# TubeBoard-Holder.net
KiCad netlist of a schematic drawn in EAGLE
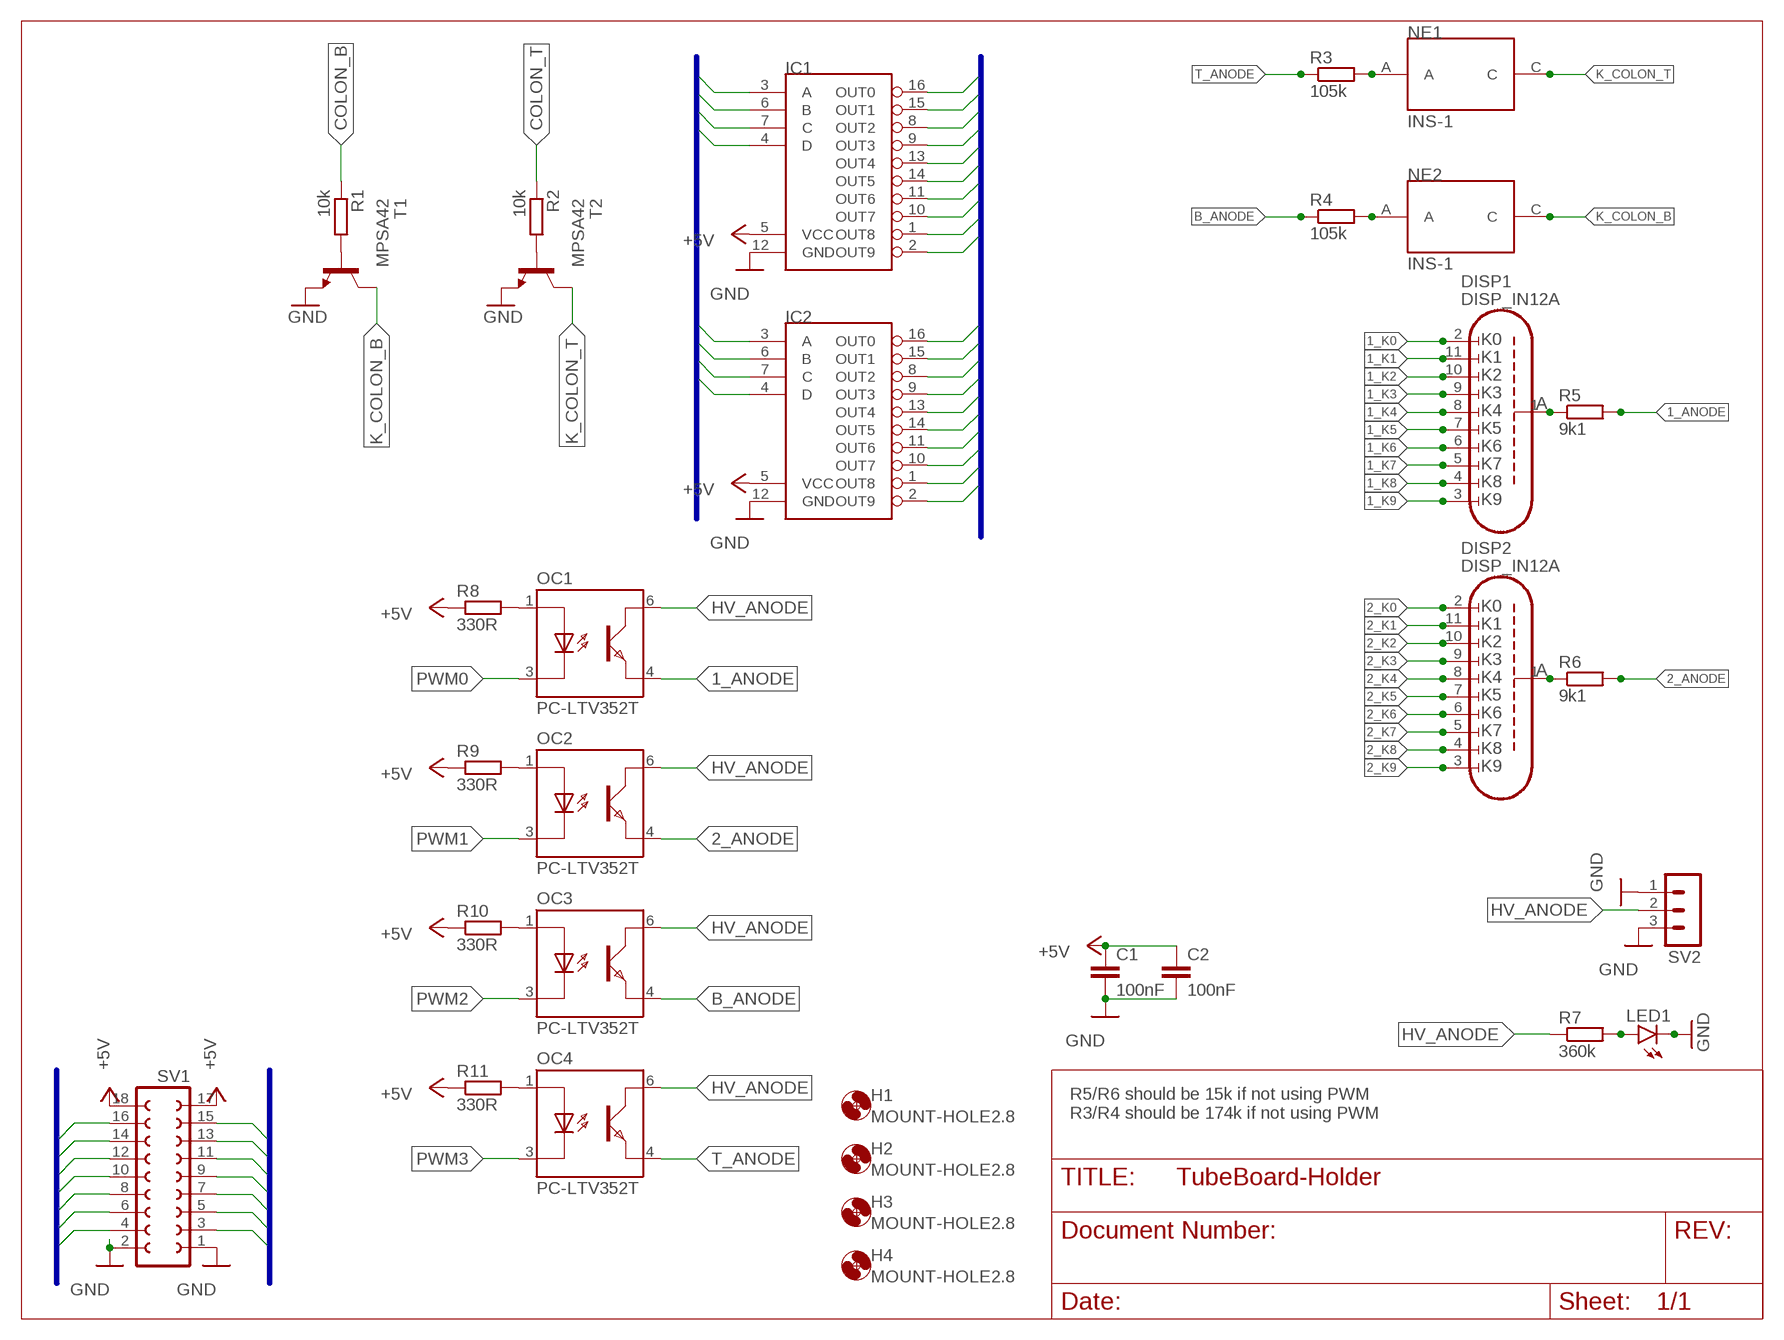
[diagram p0: schematic, sheet 1]

(export (version "E")
  (design (tool "Eeschema 10.0.6"))
  (components
    (comp (ref "C1")
      (value "100nF")
      (footprint "eagle-import:C1206")
      (libsource (lib "eagle-import") (part "C-EUC1206"))
    )
    (comp (ref "C2")
      (value "100nF")
      (footprint "eagle-import:C1206")
      (libsource (lib "eagle-import") (part "C-EUC1206"))
    )
    (comp (ref "DISP1")
      (value "DISP_IN12A")
      (footprint "eagle-import:DISP_IN-12_SOCKET")
      (libsource (lib "eagle-import") (part "DISP_IN12A"))
    )
    (comp (ref "DISP2")
      (value "DISP_IN12A")
      (footprint "eagle-import:DISP_IN-12_SOCKET")
      (libsource (lib "eagle-import") (part "DISP_IN12A"))
    )
    (comp (ref "H1")
      (value "MOUNT-HOLE2.8")
      (footprint "eagle-import:2,8")
      (libsource (lib "eagle-import") (part "MOUNT-HOLE2.8"))
    )
    (comp (ref "H2")
      (value "MOUNT-HOLE2.8")
      (footprint "eagle-import:2,8")
      (libsource (lib "eagle-import") (part "MOUNT-HOLE2.8"))
    )
    (comp (ref "H3")
      (value "MOUNT-HOLE2.8")
      (footprint "eagle-import:2,8")
      (libsource (lib "eagle-import") (part "MOUNT-HOLE2.8"))
    )
    (comp (ref "H4")
      (value "MOUNT-HOLE2.8")
      (footprint "eagle-import:2,8")
      (libsource (lib "eagle-import") (part "MOUNT-HOLE2.8"))
    )
    (comp (ref "IC1")
      (value "7441DIL16")
      (footprint "eagle-import:DIL16")
      (libsource (lib "eagle-import") (part "7441DIL16"))
    )
    (comp (ref "IC2")
      (value "7441DIL16")
      (footprint "eagle-import:DIL16")
      (libsource (lib "eagle-import") (part "7441DIL16"))
    )
    (comp (ref "LED1")
      (value "LEDCHIPLED_1206")
      (footprint "eagle-import:CHIPLED_1206")
      (libsource (lib "eagle-import") (part "LEDCHIPLED_1206"))
    )
    (comp (ref "NE1")
      (value "INS-1")
      (footprint "eagle-import:INS-1")
      (libsource (lib "eagle-import") (part "INS-1"))
    )
    (comp (ref "NE2")
      (value "INS-1")
      (footprint "eagle-import:INS-1")
      (libsource (lib "eagle-import") (part "INS-1"))
    )
    (comp (ref "OC1")
      (value "PC-LTV352T")
      (footprint "eagle-import:MINIFLAT4")
      (libsource (lib "eagle-import") (part "PC-LTV352T"))
    )
    (comp (ref "OC2")
      (value "PC-LTV352T")
      (footprint "eagle-import:MINIFLAT4")
      (libsource (lib "eagle-import") (part "PC-LTV352T"))
    )
    (comp (ref "OC3")
      (value "PC-LTV352T")
      (footprint "eagle-import:MINIFLAT4")
      (libsource (lib "eagle-import") (part "PC-LTV352T"))
    )
    (comp (ref "OC4")
      (value "PC-LTV352T")
      (footprint "eagle-import:MINIFLAT4")
      (libsource (lib "eagle-import") (part "PC-LTV352T"))
    )
    (comp (ref "R1")
      (value "10k")
      (footprint "eagle-import:R2012")
      (libsource (lib "eagle-import") (part "R-EU_R2012"))
    )
    (comp (ref "R2")
      (value "10k")
      (footprint "eagle-import:R2012")
      (libsource (lib "eagle-import") (part "R-EU_R2012"))
    )
    (comp (ref "R3")
      (value "105k")
      (footprint "eagle-import:M1206")
      (libsource (lib "eagle-import") (part "R-EU_M1206"))
    )
    (comp (ref "R4")
      (value "105k")
      (footprint "eagle-import:M1206")
      (libsource (lib "eagle-import") (part "R-EU_M1206"))
    )
    (comp (ref "R5")
      (value "9k1")
      (footprint "eagle-import:0411_12")
      (libsource (lib "eagle-import") (part "R-EU_0411/12"))
    )
    (comp (ref "R6")
      (value "9k1")
      (footprint "eagle-import:0411_12")
      (libsource (lib "eagle-import") (part "R-EU_0411/12"))
    )
    (comp (ref "R7")
      (value "360k")
      (footprint "eagle-import:R2012")
      (libsource (lib "eagle-import") (part "R-EU_R2012"))
    )
    (comp (ref "R8")
      (value "330R")
      (footprint "eagle-import:R2012")
      (libsource (lib "eagle-import") (part "R-EU_R2012"))
    )
    (comp (ref "R9")
      (value "330R")
      (footprint "eagle-import:R2012")
      (libsource (lib "eagle-import") (part "R-EU_R2012"))
    )
    (comp (ref "R10")
      (value "330R")
      (footprint "eagle-import:R2012")
      (libsource (lib "eagle-import") (part "R-EU_R2012"))
    )
    (comp (ref "R11")
      (value "330R")
      (footprint "eagle-import:R2012")
      (libsource (lib "eagle-import") (part "R-EU_R2012"))
    )
    (comp (ref "SV1")
      (value "FE09-2")
      (footprint "eagle-import:FE09-2")
      (libsource (lib "eagle-import") (part "FE09-2"))
    )
    (comp (ref "SV2")
      (value "MA03-1")
      (footprint "eagle-import:MA03-1")
      (libsource (lib "eagle-import") (part "MA03-1"))
    )
    (comp (ref "T1")
      (value "MPSA42")
      (footprint "eagle-import:TO92-EBC")
      (libsource (lib "eagle-import") (part "-NPN-TO92-EBCMPSA42"))
    )
    (comp (ref "T2")
      (value "MPSA42")
      (footprint "eagle-import:TO92-EBC")
      (libsource (lib "eagle-import") (part "-NPN-TO92-EBCMPSA42"))
    )
  )
  (nets
    (net (code "1") (name "+5V") (class "Default")
      (node (ref "C1") (pin "1") (pinfunction "1_1") (pintype "passive"))
      (node (ref "C2") (pin "1") (pinfunction "1_1") (pintype "passive"))
      (node (ref "IC1") (pin "5") (pinfunction "VCC_5") (pintype "passive"))
      (node (ref "IC2") (pin "5") (pinfunction "VCC_5") (pintype "passive"))
      (node (ref "R10") (pin "1") (pinfunction "1_1") (pintype "passive"))
      (node (ref "R11") (pin "1") (pinfunction "1_1") (pintype "passive"))
      (node (ref "R8") (pin "1") (pinfunction "1_1") (pintype "passive"))
      (node (ref "R9") (pin "1") (pinfunction "1_1") (pintype "passive"))
      (node (ref "SV1") (pin "17") (pinfunction "17_17") (pintype "passive"))
      (node (ref "SV1") (pin "18") (pinfunction "18_18") (pintype "passive"))
    )
    (net (code "2") (name "/LDIGIT0") (class "Default")
      (node (ref "IC1") (pin "3") (pinfunction "A_3") (pintype "input"))
      (node (ref "SV1") (pin "16") (pinfunction "16_16") (pintype "passive"))
    )
    (net (code "3") (name "/LDIGIT1") (class "Default")
      (node (ref "IC1") (pin "6") (pinfunction "B_6") (pintype "input"))
      (node (ref "SV1") (pin "14") (pinfunction "14_14") (pintype "passive"))
    )
    (net (code "4") (name "/LDIGIT2") (class "Default")
      (node (ref "IC1") (pin "7") (pinfunction "C_7") (pintype "input"))
      (node (ref "SV1") (pin "12") (pinfunction "12_12") (pintype "passive"))
    )
    (net (code "5") (name "/LDIGIT3") (class "Default")
      (node (ref "IC1") (pin "4") (pinfunction "D_4") (pintype "input"))
      (node (ref "SV1") (pin "10") (pinfunction "10_10") (pintype "passive"))
    )
    (net (code "6") (name "/RDIGIT0") (class "Default")
      (node (ref "IC2") (pin "3") (pinfunction "A_3") (pintype "input"))
      (node (ref "SV1") (pin "15") (pinfunction "15_15") (pintype "passive"))
    )
    (net (code "7") (name "/RDIGIT1") (class "Default")
      (node (ref "IC2") (pin "6") (pinfunction "B_6") (pintype "input"))
      (node (ref "SV1") (pin "13") (pinfunction "13_13") (pintype "passive"))
    )
    (net (code "8") (name "/RDIGIT2") (class "Default")
      (node (ref "IC2") (pin "7") (pinfunction "C_7") (pintype "input"))
      (node (ref "SV1") (pin "11") (pinfunction "11_11") (pintype "passive"))
    )
    (net (code "9") (name "/RDIGIT3") (class "Default")
      (node (ref "IC2") (pin "4") (pinfunction "D_4") (pintype "input"))
      (node (ref "SV1") (pin "9") (pinfunction "9_9") (pintype "passive"))
    )
    (net (code "11") (name "1_ANODE") (class "Default")
      (node (ref "OC1") (pin "4") (pinfunction "TE_4") (pintype "bidirectional"))
      (node (ref "R5") (pin "2") (pinfunction "2_2") (pintype "passive"))
    )
    (net (code "12") (name "1_K0") (class "Default")
      (node (ref "DISP1") (pin "2") (pinfunction "K0_2") (pintype "input"))
      (node (ref "IC1") (pin "16") (pinfunction "OUT0_16") (pintype "output"))
    )
    (net (code "13") (name "1_K1") (class "Default")
      (node (ref "DISP1") (pin "11") (pinfunction "K1_11") (pintype "input"))
      (node (ref "IC1") (pin "15") (pinfunction "OUT1_15") (pintype "output"))
    )
    (net (code "14") (name "1_K2") (class "Default")
      (node (ref "DISP1") (pin "10") (pinfunction "K2_10") (pintype "input"))
      (node (ref "IC1") (pin "8") (pinfunction "OUT2_8") (pintype "output"))
    )
    (net (code "15") (name "1_K3") (class "Default")
      (node (ref "DISP1") (pin "9") (pinfunction "K3_9") (pintype "input"))
      (node (ref "IC1") (pin "9") (pinfunction "OUT3_9") (pintype "output"))
    )
    (net (code "16") (name "1_K4") (class "Default")
      (node (ref "DISP1") (pin "8") (pinfunction "K4_8") (pintype "input"))
      (node (ref "IC1") (pin "13") (pinfunction "OUT4_13") (pintype "output"))
    )
    (net (code "17") (name "1_K5") (class "Default")
      (node (ref "DISP1") (pin "7") (pinfunction "K5_7") (pintype "input"))
      (node (ref "IC1") (pin "14") (pinfunction "OUT5_14") (pintype "output"))
    )
    (net (code "18") (name "1_K6") (class "Default")
      (node (ref "DISP1") (pin "6") (pinfunction "K6_6") (pintype "input"))
      (node (ref "IC1") (pin "11") (pinfunction "OUT6_11") (pintype "output"))
    )
    (net (code "19") (name "1_K7") (class "Default")
      (node (ref "DISP1") (pin "5") (pinfunction "K7_5") (pintype "input"))
      (node (ref "IC1") (pin "10") (pinfunction "OUT7_10") (pintype "output"))
    )
    (net (code "20") (name "1_K8") (class "Default")
      (node (ref "DISP1") (pin "4") (pinfunction "K8_4") (pintype "input"))
      (node (ref "IC1") (pin "1") (pinfunction "OUT8_1") (pintype "output"))
    )
    (net (code "21") (name "1_K9") (class "Default")
      (node (ref "DISP1") (pin "3") (pinfunction "K9_3") (pintype "input"))
      (node (ref "IC1") (pin "2") (pinfunction "OUT9_2") (pintype "output"))
    )
    (net (code "22") (name "2_ANODE") (class "Default")
      (node (ref "OC2") (pin "4") (pinfunction "TE_4") (pintype "bidirectional"))
      (node (ref "R6") (pin "2") (pinfunction "2_2") (pintype "passive"))
    )
    (net (code "23") (name "2_K0") (class "Default")
      (node (ref "DISP2") (pin "2") (pinfunction "K0_2") (pintype "input"))
      (node (ref "IC2") (pin "16") (pinfunction "OUT0_16") (pintype "output"))
    )
    (net (code "24") (name "2_K1") (class "Default")
      (node (ref "DISP2") (pin "11") (pinfunction "K1_11") (pintype "input"))
      (node (ref "IC2") (pin "15") (pinfunction "OUT1_15") (pintype "output"))
    )
    (net (code "25") (name "2_K2") (class "Default")
      (node (ref "DISP2") (pin "10") (pinfunction "K2_10") (pintype "input"))
      (node (ref "IC2") (pin "8") (pinfunction "OUT2_8") (pintype "output"))
    )
    (net (code "26") (name "2_K3") (class "Default")
      (node (ref "DISP2") (pin "9") (pinfunction "K3_9") (pintype "input"))
      (node (ref "IC2") (pin "9") (pinfunction "OUT3_9") (pintype "output"))
    )
    (net (code "27") (name "2_K4") (class "Default")
      (node (ref "DISP2") (pin "8") (pinfunction "K4_8") (pintype "input"))
      (node (ref "IC2") (pin "13") (pinfunction "OUT4_13") (pintype "output"))
    )
    (net (code "28") (name "2_K5") (class "Default")
      (node (ref "DISP2") (pin "7") (pinfunction "K5_7") (pintype "input"))
      (node (ref "IC2") (pin "14") (pinfunction "OUT5_14") (pintype "output"))
    )
    (net (code "29") (name "2_K6") (class "Default")
      (node (ref "DISP2") (pin "6") (pinfunction "K6_6") (pintype "input"))
      (node (ref "IC2") (pin "11") (pinfunction "OUT6_11") (pintype "output"))
    )
    (net (code "30") (name "2_K7") (class "Default")
      (node (ref "DISP2") (pin "5") (pinfunction "K7_5") (pintype "input"))
      (node (ref "IC2") (pin "10") (pinfunction "OUT7_10") (pintype "output"))
    )
    (net (code "31") (name "2_K8") (class "Default")
      (node (ref "DISP2") (pin "4") (pinfunction "K8_4") (pintype "input"))
      (node (ref "IC2") (pin "1") (pinfunction "OUT8_1") (pintype "output"))
    )
    (net (code "32") (name "2_K9") (class "Default")
      (node (ref "DISP2") (pin "3") (pinfunction "K9_3") (pintype "input"))
      (node (ref "IC2") (pin "2") (pinfunction "OUT9_2") (pintype "output"))
    )
    (net (code "33") (name "B_ANODE") (class "Default")
      (node (ref "OC3") (pin "4") (pinfunction "TE_4") (pintype "bidirectional"))
      (node (ref "R4") (pin "1") (pinfunction "1_1") (pintype "passive"))
    )
    (net (code "34") (name "COLON_B") (class "Default")
      (node (ref "R1") (pin "1") (pinfunction "1_1") (pintype "passive"))
      (node (ref "SV1") (pin "8") (pinfunction "8_8") (pintype "passive"))
    )
    (net (code "35") (name "COLON_T") (class "Default")
      (node (ref "R2") (pin "1") (pinfunction "1_1") (pintype "passive"))
      (node (ref "SV1") (pin "6") (pinfunction "6_6") (pintype "passive"))
    )
    (net (code "36") (name "GND") (class "Default")
      (node (ref "C1") (pin "2") (pinfunction "2_2") (pintype "passive"))
      (node (ref "C2") (pin "2") (pinfunction "2_2") (pintype "passive"))
      (node (ref "IC1") (pin "12") (pinfunction "GND_12") (pintype "passive"))
      (node (ref "IC2") (pin "12") (pinfunction "GND_12") (pintype "passive"))
      (node (ref "LED1") (pin "C") (pinfunction "C_C") (pintype "passive"))
      (node (ref "SV1") (pin "1") (pinfunction "1_1") (pintype "passive"))
      (node (ref "SV1") (pin "2") (pinfunction "2_2") (pintype "passive"))
      (node (ref "SV2") (pin "1") (pinfunction "1_1") (pintype "passive"))
      (node (ref "SV2") (pin "3") (pinfunction "3_3") (pintype "passive"))
      (node (ref "T1") (pin "E") (pinfunction "E_E") (pintype "passive"))
      (node (ref "T2") (pin "E") (pinfunction "E_E") (pintype "passive"))
    )
    (net (code "37") (name "HV_ANODE") (class "Default")
      (node (ref "OC1") (pin "6") (pinfunction "TC_6") (pintype "bidirectional"))
      (node (ref "OC2") (pin "6") (pinfunction "TC_6") (pintype "bidirectional"))
      (node (ref "OC3") (pin "6") (pinfunction "TC_6") (pintype "bidirectional"))
      (node (ref "OC4") (pin "6") (pinfunction "TC_6") (pintype "bidirectional"))
      (node (ref "R7") (pin "1") (pinfunction "1_1") (pintype "passive"))
      (node (ref "SV2") (pin "2") (pinfunction "2_2") (pintype "passive"))
    )
    (net (code "38") (name "K_COLON_B") (class "Default")
      (node (ref "NE2") (pin "C") (pinfunction "C_C") (pintype "bidirectional"))
      (node (ref "T1") (pin "C") (pinfunction "C_C") (pintype "passive"))
    )
    (net (code "39") (name "K_COLON_T") (class "Default")
      (node (ref "NE1") (pin "C") (pinfunction "C_C") (pintype "bidirectional"))
      (node (ref "T2") (pin "C") (pinfunction "C_C") (pintype "passive"))
    )
    (net (code "40") (name "Net-(DISP1-ANODE)") (class "Default")
      (node (ref "DISP1") (pin "1") (pinfunction "ANODE_1") (pintype "input"))
      (node (ref "R5") (pin "1") (pinfunction "1_1") (pintype "passive"))
    )
    (net (code "41") (name "Net-(DISP2-ANODE)") (class "Default")
      (node (ref "DISP2") (pin "1") (pinfunction "ANODE_1") (pintype "input"))
      (node (ref "R6") (pin "1") (pinfunction "1_1") (pintype "passive"))
    )
    (net (code "42") (name "Net-(LED1-PadA)") (class "Default")
      (node (ref "LED1") (pin "A") (pinfunction "A_A") (pintype "passive"))
      (node (ref "R7") (pin "2") (pinfunction "2_2") (pintype "passive"))
    )
    (net (code "43") (name "Net-(NE1-PadA)") (class "Default")
      (node (ref "NE1") (pin "A") (pinfunction "A_A") (pintype "bidirectional"))
      (node (ref "R3") (pin "2") (pinfunction "2_2") (pintype "passive"))
    )
    (net (code "44") (name "Net-(NE2-PadA)") (class "Default")
      (node (ref "NE2") (pin "A") (pinfunction "A_A") (pintype "bidirectional"))
      (node (ref "R4") (pin "2") (pinfunction "2_2") (pintype "passive"))
    )
    (net (code "45") (name "Net-(OC1-A)") (class "Default")
      (node (ref "OC1") (pin "1") (pinfunction "A_1") (pintype "bidirectional"))
      (node (ref "R8") (pin "2") (pinfunction "2_2") (pintype "passive"))
    )
    (net (code "46") (name "Net-(OC2-A)") (class "Default")
      (node (ref "OC2") (pin "1") (pinfunction "A_1") (pintype "bidirectional"))
      (node (ref "R9") (pin "2") (pinfunction "2_2") (pintype "passive"))
    )
    (net (code "47") (name "Net-(OC3-A)") (class "Default")
      (node (ref "OC3") (pin "1") (pinfunction "A_1") (pintype "bidirectional"))
      (node (ref "R10") (pin "2") (pinfunction "2_2") (pintype "passive"))
    )
    (net (code "48") (name "Net-(OC4-A)") (class "Default")
      (node (ref "OC4") (pin "1") (pinfunction "A_1") (pintype "bidirectional"))
      (node (ref "R11") (pin "2") (pinfunction "2_2") (pintype "passive"))
    )
    (net (code "49") (name "Net-(R1-Pad2)") (class "Default")
      (node (ref "R1") (pin "2") (pinfunction "2_2") (pintype "passive"))
      (node (ref "T1") (pin "B") (pinfunction "B_B") (pintype "passive"))
    )
    (net (code "50") (name "Net-(R2-Pad2)") (class "Default")
      (node (ref "R2") (pin "2") (pinfunction "2_2") (pintype "passive"))
      (node (ref "T2") (pin "B") (pinfunction "B_B") (pintype "passive"))
    )
    (net (code "51") (name "PWM0") (class "Default")
      (node (ref "OC1") (pin "3") (pinfunction "C_3") (pintype "bidirectional"))
      (node (ref "SV1") (pin "7") (pinfunction "7_7") (pintype "passive"))
    )
    (net (code "52") (name "PWM1") (class "Default")
      (node (ref "OC2") (pin "3") (pinfunction "C_3") (pintype "bidirectional"))
      (node (ref "SV1") (pin "5") (pinfunction "5_5") (pintype "passive"))
    )
    (net (code "53") (name "PWM2") (class "Default")
      (node (ref "OC3") (pin "3") (pinfunction "C_3") (pintype "bidirectional"))
      (node (ref "SV1") (pin "3") (pinfunction "3_3") (pintype "passive"))
    )
    (net (code "54") (name "PWM3") (class "Default")
      (node (ref "OC4") (pin "3") (pinfunction "C_3") (pintype "bidirectional"))
      (node (ref "SV1") (pin "4") (pinfunction "4_4") (pintype "passive"))
    )
    (net (code "55") (name "T_ANODE") (class "Default")
      (node (ref "OC4") (pin "4") (pinfunction "TE_4") (pintype "bidirectional"))
      (node (ref "R3") (pin "1") (pinfunction "1_1") (pintype "passive"))
    )
  )
)
